# 0068_Marquee.net
KiCad netlist of a schematic drawn in Altium Designer
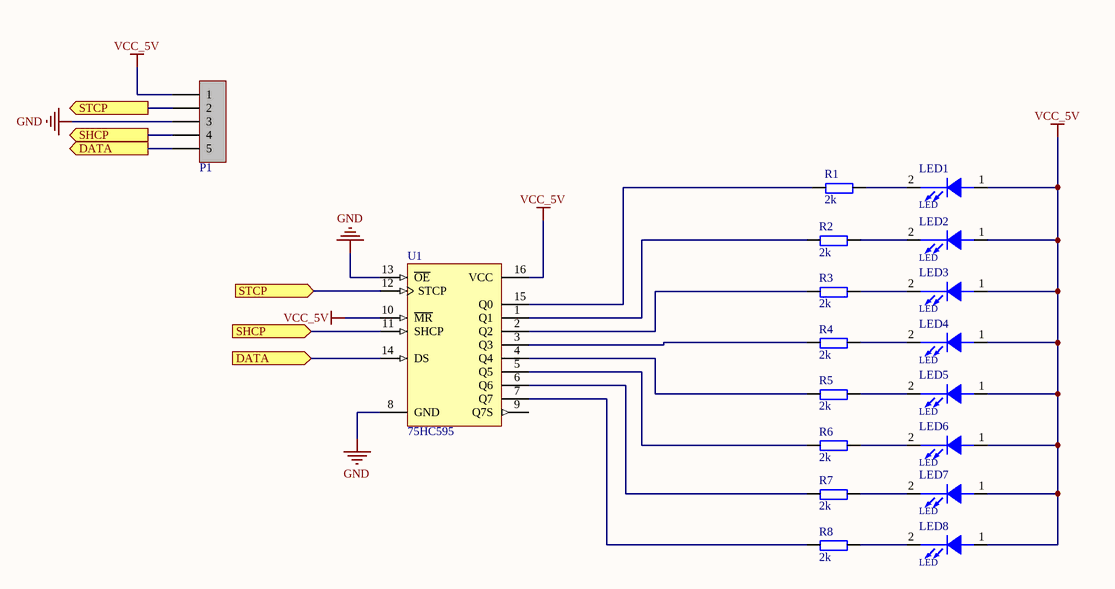
[diagram p0: 0068_Marquee.SchDoc]

(export (version "E")
  (design (tool "Eeschema 10.0.6"))
  (components
    (comp (ref "LED1") (value "LED") (footprint "SMDLED-0603") (libsource (lib "Control Board") (part "LED")))
    (comp (ref "LED2") (value "LED") (footprint "SMDLED-0603") (libsource (lib "Control Board") (part "LED")))
    (comp (ref "LED3") (value "LED") (footprint "SMDLED-0603") (libsource (lib "Control Board") (part "LED")))
    (comp (ref "LED4") (value "LED") (footprint "SMDLED-0603") (libsource (lib "Control Board") (part "LED")))
    (comp (ref "LED5") (value "LED") (footprint "SMDLED-0603") (libsource (lib "Control Board") (part "LED")))
    (comp (ref "LED6") (value "LED") (footprint "SMDLED-0603") (libsource (lib "Control Board") (part "LED")))
    (comp (ref "LED7") (value "LED") (footprint "SMDLED-0603") (libsource (lib "Control Board") (part "LED")))
    (comp (ref "LED8") (value "LED") (footprint "SMDLED-0603") (libsource (lib "Control Board") (part "LED")))
    (comp (ref "P1")
      (value "CON5_1")
      (footprint "HDR5X1_B")
      (description "Connector")
      (libsource (lib "Control Board") (part "CON5_1"))
    )
    (comp (ref "R1")
      (value "2k")
      (footprint "0603P")
      (description "贴片电阻")
      (libsource (lib "Control Board") (part "R"))
    )
    (comp (ref "R2")
      (value "2k")
      (footprint "0603P")
      (description "贴片电阻")
      (libsource (lib "Control Board") (part "R"))
    )
    (comp (ref "R3")
      (value "2k")
      (footprint "0603P")
      (description "贴片电阻")
      (libsource (lib "Control Board") (part "R"))
    )
    (comp (ref "R4")
      (value "2k")
      (footprint "0603P")
      (description "贴片电阻")
      (libsource (lib "Control Board") (part "R"))
    )
    (comp (ref "R5")
      (value "2k")
      (footprint "0603P")
      (description "贴片电阻")
      (libsource (lib "Control Board") (part "R"))
    )
    (comp (ref "R6")
      (value "2k")
      (footprint "0603P")
      (description "贴片电阻")
      (libsource (lib "Control Board") (part "R"))
    )
    (comp (ref "R7")
      (value "2k")
      (footprint "0603P")
      (description "贴片电阻")
      (libsource (lib "Control Board") (part "R"))
    )
    (comp (ref "R8")
      (value "2k")
      (footprint "0603P")
      (description "贴片电阻")
      (libsource (lib "Control Board") (part "R"))
    )
    (comp (ref "U1")
      (value "75HC595")
      (footprint "SOT763-1")
      (description "IC 8BIT SHIFT REGISTER 16-DHVQFN")
      (libsource (lib "CJ_Component") (part "74HC595"))
    )
  )
  (nets
    (net (code "1") (name "/DATA") (class "Default")
      (node (ref "P1") (pin "5") (pinfunction "5_5") (pintype "passive"))
      (node (ref "U1") (pin "14") (pinfunction "DS_14") (pintype "input"))
    )
    (net (code "2") (name "/SHCP") (class "Default")
      (node (ref "P1") (pin "4") (pinfunction "4_4") (pintype "passive"))
      (node (ref "U1") (pin "11") (pinfunction "SHCP_11") (pintype "input"))
    )
    (net (code "3") (name "/STCP") (class "Default")
      (node (ref "P1") (pin "2") (pinfunction "2_2") (pintype "passive"))
      (node (ref "U1") (pin "12") (pinfunction "STCP_12") (pintype "input"))
    )
    (net (code "4") (name "GND") (class "Default")
      (node (ref "P1") (pin "3") (pinfunction "3_3") (pintype "passive"))
      (node (ref "U1") (pin "13") (pinfunction "~{OE}_13") (pintype "input"))
      (node (ref "U1") (pin "8") (pinfunction "GND_8") (pintype "power_in"))
    )
    (net (code "5") (name "Net-(LED1-CATHODE)") (class "Default")
      (node (ref "LED1") (pin "2") (pinfunction "CATHODE_2") (pintype "passive"))
      (node (ref "R1") (pin "2") (pintype "passive"))
    )
    (net (code "6") (name "Net-(LED2-CATHODE)") (class "Default")
      (node (ref "LED2") (pin "2") (pinfunction "CATHODE_2") (pintype "passive"))
      (node (ref "R2") (pin "2") (pintype "passive"))
    )
    (net (code "7") (name "Net-(LED3-CATHODE)") (class "Default")
      (node (ref "LED3") (pin "2") (pinfunction "CATHODE_2") (pintype "passive"))
      (node (ref "R3") (pin "2") (pintype "passive"))
    )
    (net (code "8") (name "Net-(LED4-CATHODE)") (class "Default")
      (node (ref "LED4") (pin "2") (pinfunction "CATHODE_2") (pintype "passive"))
      (node (ref "R4") (pin "2") (pintype "passive"))
    )
    (net (code "9") (name "Net-(LED5-CATHODE)") (class "Default")
      (node (ref "LED5") (pin "2") (pinfunction "CATHODE_2") (pintype "passive"))
      (node (ref "R5") (pin "2") (pintype "passive"))
    )
    (net (code "10") (name "Net-(LED6-CATHODE)") (class "Default")
      (node (ref "LED6") (pin "2") (pinfunction "CATHODE_2") (pintype "passive"))
      (node (ref "R6") (pin "2") (pintype "passive"))
    )
    (net (code "11") (name "Net-(LED7-CATHODE)") (class "Default")
      (node (ref "LED7") (pin "2") (pinfunction "CATHODE_2") (pintype "passive"))
      (node (ref "R7") (pin "2") (pintype "passive"))
    )
    (net (code "12") (name "Net-(LED8-CATHODE)") (class "Default")
      (node (ref "LED8") (pin "2") (pinfunction "CATHODE_2") (pintype "passive"))
      (node (ref "R8") (pin "2") (pintype "passive"))
    )
    (net (code "13") (name "Net-(U1-Q0)") (class "Default")
      (node (ref "R1") (pin "1") (pintype "passive"))
      (node (ref "U1") (pin "15") (pinfunction "Q0_15") (pintype "tri_state"))
    )
    (net (code "14") (name "Net-(U1-Q1)") (class "Default")
      (node (ref "R2") (pin "1") (pintype "passive"))
      (node (ref "U1") (pin "1") (pinfunction "Q1_1") (pintype "tri_state"))
    )
    (net (code "15") (name "Net-(U1-Q2)") (class "Default")
      (node (ref "R3") (pin "1") (pintype "passive"))
      (node (ref "U1") (pin "2") (pinfunction "Q2_2") (pintype "tri_state"))
    )
    (net (code "16") (name "Net-(U1-Q3)") (class "Default")
      (node (ref "R4") (pin "1") (pintype "passive"))
      (node (ref "U1") (pin "3") (pinfunction "Q3_3") (pintype "tri_state"))
    )
    (net (code "17") (name "Net-(U1-Q4)") (class "Default")
      (node (ref "R5") (pin "1") (pintype "passive"))
      (node (ref "U1") (pin "4") (pinfunction "Q4_4") (pintype "tri_state"))
    )
    (net (code "18") (name "Net-(U1-Q5)") (class "Default")
      (node (ref "R6") (pin "1") (pintype "passive"))
      (node (ref "U1") (pin "5") (pinfunction "Q5_5") (pintype "tri_state"))
    )
    (net (code "19") (name "Net-(U1-Q6)") (class "Default")
      (node (ref "R7") (pin "1") (pintype "passive"))
      (node (ref "U1") (pin "6") (pinfunction "Q6_6") (pintype "tri_state"))
    )
    (net (code "20") (name "Net-(U1-Q7)") (class "Default")
      (node (ref "R8") (pin "1") (pintype "passive"))
      (node (ref "U1") (pin "7") (pinfunction "Q7_7") (pintype "tri_state"))
    )
    (net (code "21") (name "VCC_5V") (class "Default")
      (node (ref "LED1") (pin "1") (pinfunction "ANODE_1") (pintype "passive"))
      (node (ref "LED2") (pin "1") (pinfunction "ANODE_1") (pintype "passive"))
      (node (ref "LED3") (pin "1") (pinfunction "ANODE_1") (pintype "passive"))
      (node (ref "LED4") (pin "1") (pinfunction "ANODE_1") (pintype "passive"))
      (node (ref "LED5") (pin "1") (pinfunction "ANODE_1") (pintype "passive"))
      (node (ref "LED6") (pin "1") (pinfunction "ANODE_1") (pintype "passive"))
      (node (ref "LED7") (pin "1") (pinfunction "ANODE_1") (pintype "passive"))
      (node (ref "LED8") (pin "1") (pinfunction "ANODE_1") (pintype "passive"))
      (node (ref "P1") (pin "1") (pinfunction "1_1") (pintype "passive"))
      (node (ref "U1") (pin "10") (pinfunction "~{MR}_10") (pintype "input"))
      (node (ref "U1") (pin "16") (pinfunction "VCC_16") (pintype "power_in"))
    )
    (net (code "22") (name "unconnected-(U1-Q7S-Pad9)") (class "Default")
      (node (ref "U1") (pin "9") (pinfunction "Q7S_9") (pintype "output"))
    )
  )
)
